# Interface_-_Programmer.net
KiCad netlist of a schematic drawn in Altium Designer
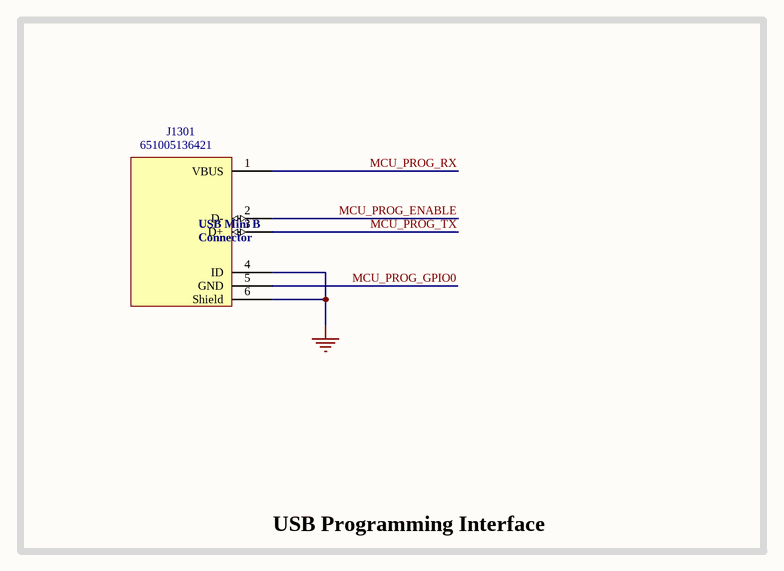
[diagram p0: Interface - Programmer.SchDoc]

(export (version "E")
  (design (tool "Eeschema 10.0.6"))
  (components
    (comp (ref "J1301")
      (value "651005136421")
      (footprint "651005136421")
      (description "USB Connectors WR-COM Type B 5Pin Vert Feml Mini")
      (libsource (lib "Schematic-Lib") (part "651005136421"))
    )
  )
  (nets
    (net (code "1") (name "/MCU_PROG_ENABLE") (class "Default")
      (node (ref "J1301") (pin "2") (pinfunction "D-_2") (pintype "bidirectional"))
    )
    (net (code "2") (name "/MCU_PROG_GPIO0") (class "Default")
      (node (ref "J1301") (pin "5") (pinfunction "GND_5") (pintype "passive"))
    )
    (net (code "3") (name "/MCU_PROG_RX") (class "Default")
      (node (ref "J1301") (pin "1") (pinfunction "VBUS_1") (pintype "power_in"))
    )
    (net (code "4") (name "/MCU_PROG_TX") (class "Default")
      (node (ref "J1301") (pin "3") (pinfunction "D+_3") (pintype "bidirectional"))
    )
    (net (code "5") (name "GND") (class "Default")
      (node (ref "J1301") (pin "4") (pinfunction "ID_4") (pintype "passive"))
      (node (ref "J1301") (pin "6") (pinfunction "Shield_6") (pintype "passive"))
    )
  )
)
